# WR_LINK.net
KiCad netlist of a schematic drawn in Altium Designer
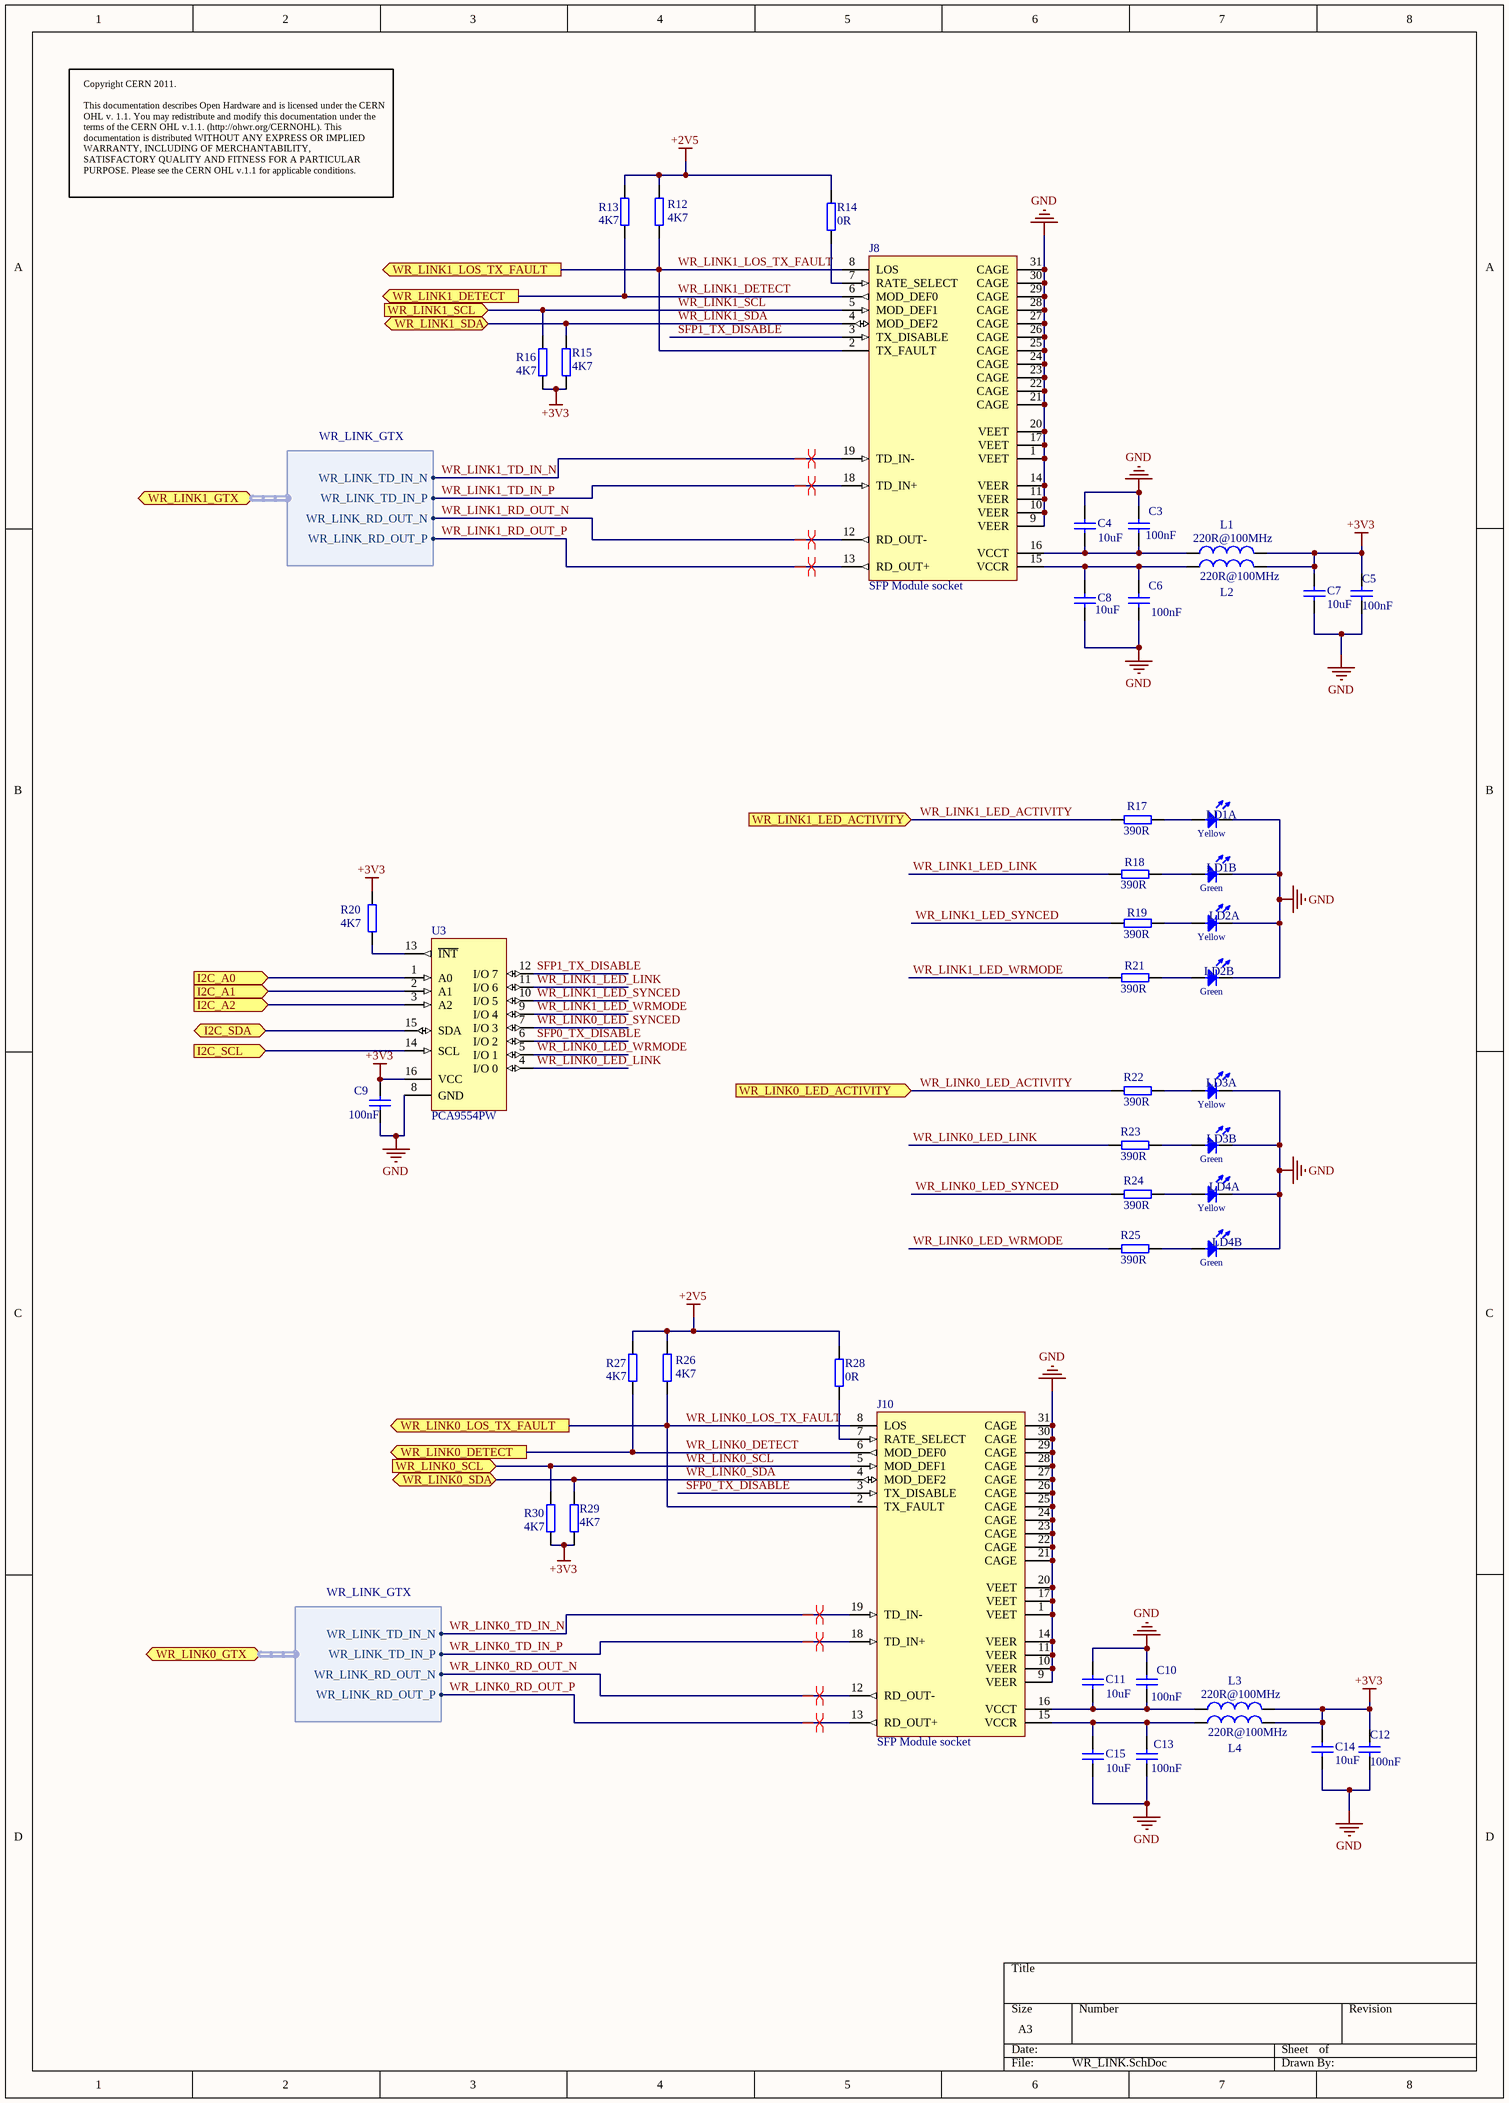
[diagram p0: WR_LINK.SchDoc]

(export (version "E")
  (design (tool "Eeschema 10.0.6"))
  (components
    (comp (ref "C3")
      (value "100nF")
      (footprint "CC1608-0603")
      (description "Capacitor")
      (fields
        (field (name "TOLERANCE") "±10%")
        (field (name "VOLTAGE") "16V")
        (field (name "PUBLISHER") "Altium Limited")
      )
      (libsource (lib "wr_switch") (part "Cap"))
    )
    (comp (ref "C4")
      (value "10uF")
      (footprint "CC2012-0805")
      (description "Capacitor")
      (fields
        (field (name "TOLERANCE") "±10%")
        (field (name "VOLTAGE") "16V")
        (field (name "PUBLISHER") "Altium Limited")
      )
      (libsource (lib "wr_switch") (part "Cap"))
    )
    (comp (ref "C5")
      (value "100nF")
      (footprint "CC1608-0603")
      (description "Capacitor")
      (fields
        (field (name "TOLERANCE") "±10%")
        (field (name "VOLTAGE") "16V")
        (field (name "PUBLISHER") "Altium Limited")
      )
      (libsource (lib "wr_switch") (part "Cap"))
    )
    (comp (ref "C6")
      (value "100nF")
      (footprint "CC1608-0603")
      (description "Capacitor")
      (fields
        (field (name "TOLERANCE") "±10%")
        (field (name "VOLTAGE") "16V")
        (field (name "PUBLISHER") "Altium Limited")
      )
      (libsource (lib "wr_switch") (part "Cap"))
    )
    (comp (ref "C7")
      (value "10uF")
      (footprint "CC1608-0603")
      (description "Capacitor")
      (fields
        (field (name "TOLERANCE") "±20%")
        (field (name "VOLTAGE") "6.3V")
        (field (name "PUBLISHER") "Altium Limited")
      )
      (libsource (lib "wr_switch") (part "Cap"))
    )
    (comp (ref "C8")
      (value "10uF")
      (footprint "CC2012-0805")
      (description "Capacitor")
      (fields
        (field (name "TOLERANCE") "±10%")
        (field (name "VOLTAGE") "16V")
        (field (name "PUBLISHER") "Altium Limited")
      )
      (libsource (lib "wr_switch") (part "Cap"))
    )
    (comp (ref "C9")
      (value "100nF")
      (footprint "CC1608-0603")
      (description "Capacitor")
      (fields
        (field (name "TOLERANCE") "±10%")
        (field (name "VOLTAGE") "16V")
        (field (name "PUBLISHER") "Altium Limited")
      )
      (libsource (lib "wr_switch") (part "Cap"))
    )
    (comp (ref "C10")
      (value "100nF")
      (footprint "CC1608-0603")
      (description "Capacitor")
      (fields
        (field (name "TOLERANCE") "±10%")
        (field (name "VOLTAGE") "16V")
        (field (name "PUBLISHER") "Altium Limited")
      )
      (libsource (lib "wr_switch") (part "Cap"))
    )
    (comp (ref "C11")
      (value "10uF")
      (footprint "CC2012-0805")
      (description "Capacitor")
      (fields
        (field (name "TOLERANCE") "±10%")
        (field (name "VOLTAGE") "16V")
        (field (name "PUBLISHER") "Altium Limited")
      )
      (libsource (lib "wr_switch") (part "Cap"))
    )
    (comp (ref "C12")
      (value "100nF")
      (footprint "CC1608-0603")
      (description "Capacitor")
      (fields
        (field (name "TOLERANCE") "±10%")
        (field (name "VOLTAGE") "16V")
        (field (name "PUBLISHER") "Altium Limited")
      )
      (libsource (lib "wr_switch") (part "Cap"))
    )
    (comp (ref "C13")
      (value "100nF")
      (footprint "CC1608-0603")
      (description "Capacitor")
      (fields
        (field (name "TOLERANCE") "±10%")
        (field (name "VOLTAGE") "16V")
        (field (name "PUBLISHER") "Altium Limited")
      )
      (libsource (lib "wr_switch") (part "Cap"))
    )
    (comp (ref "C14")
      (value "10uF")
      (footprint "CC1608-0603")
      (description "Capacitor")
      (fields
        (field (name "TOLERANCE") "±20%")
        (field (name "VOLTAGE") "6.3V")
        (field (name "PUBLISHER") "Altium Limited")
      )
      (libsource (lib "wr_switch") (part "Cap"))
    )
    (comp (ref "C15")
      (value "10uF")
      (footprint "CC2012-0805")
      (description "Capacitor")
      (fields
        (field (name "TOLERANCE") "±10%")
        (field (name "VOLTAGE") "16V")
        (field (name "PUBLISHER") "Altium Limited")
      )
      (libsource (lib "wr_switch") (part "Cap"))
    )
    (comp (ref "J8")
      (value "SFP Module socket")
      (footprint "7S_WR:SFP_SINGLE_PORT")
      (description "Socket for SFP module")
      (libsource (lib "wr_switch") (part "SFP_SOCKET_SINGLE"))
    )
    (comp (ref "J10")
      (value "SFP Module socket")
      (footprint "7S_WR:SFP_SINGLE_PORT")
      (description "Socket for SFP module")
      (libsource (lib "wr_switch") (part "SFP_SOCKET_SINGLE"))
    )
    (comp (ref "L1")
      (value "220R@100MHz Ferrite Bead")
      (footprint "0603")
      (description "ferrite bead")
      (fields (field (name "IMPEDANCE") "220R@100MHz"))
      (libsource (lib "wr_switch") (part "L_FERRITE_BEAD"))
    )
    (comp (ref "L2")
      (value "220R@100MHz Ferrite Bead")
      (footprint "0603")
      (description "ferrite bead")
      (fields (field (name "IMPEDANCE") "220R@100MHz"))
      (libsource (lib "wr_switch") (part "L_FERRITE_BEAD"))
    )
    (comp (ref "L3")
      (value "220R@100MHz Ferrite Bead")
      (footprint "0603")
      (description "ferrite bead")
      (fields (field (name "IMPEDANCE") "220R@100MHz"))
      (libsource (lib "wr_switch") (part "L_FERRITE_BEAD"))
    )
    (comp (ref "L4")
      (value "220R@100MHz Ferrite Bead")
      (footprint "0603")
      (description "ferrite bead")
      (fields (field (name "IMPEDANCE") "220R@100MHz"))
      (libsource (lib "wr_switch") (part "L_FERRITE_BEAD"))
    )
    (comp (ref "LD1")
      (value "Green/Yellow")
      (footprint "7S_WR:LED_DIALIGHT_591-3x0x-0xx")
      (description "Bi-Color LED SMD")
      (libsource (lib "wr_switch") (part "LED_DIALIGHT_591-3x0x"))
    )
    (comp (ref "LD2")
      (value "Green/Yellow")
      (footprint "7S_WR:LED_DIALIGHT_591-3x0x-0xx")
      (description "Bi-Color LED SMD")
      (libsource (lib "wr_switch") (part "LED_DIALIGHT_591-3x0x"))
    )
    (comp (ref "LD3")
      (value "Green/Yellow")
      (footprint "7S_WR:LED_DIALIGHT_591-3x0x-0xx")
      (description "Bi-Color LED SMD")
      (libsource (lib "wr_switch") (part "LED_DIALIGHT_591-3x0x"))
    )
    (comp (ref "LD4")
      (value "Green/Yellow")
      (footprint "7S_WR:LED_DIALIGHT_591-3x0x-0xx")
      (description "Bi-Color LED SMD")
      (libsource (lib "wr_switch") (part "LED_DIALIGHT_591-3x0x"))
    )
    (comp (ref "R12")
      (value "4K7")
      (footprint "0603")
      (description "SMD Resistor")
      (fields (field (name "TOLERANCE") "±1%"))
      (libsource (lib "wr_switch") (part "RES_SMD"))
    )
    (comp (ref "R13")
      (value "4K7")
      (footprint "0603")
      (description "SMD Resistor")
      (fields (field (name "TOLERANCE") "±1%"))
      (libsource (lib "wr_switch") (part "RES_SMD"))
    )
    (comp (ref "R14")
      (value "0R")
      (footprint "0603")
      (description "SMD Resistor")
      (libsource (lib "wr_switch") (part "RES_SMD"))
    )
    (comp (ref "R15")
      (value "4K7")
      (footprint "0603")
      (description "SMD Resistor")
      (fields (field (name "TOLERANCE") "±1%"))
      (libsource (lib "wr_switch") (part "RES_SMD"))
    )
    (comp (ref "R16")
      (value "4K7")
      (footprint "0603")
      (description "SMD Resistor")
      (fields (field (name "TOLERANCE") "±1%"))
      (libsource (lib "wr_switch") (part "RES_SMD"))
    )
    (comp (ref "R17")
      (value "390R")
      (footprint "0603")
      (description "SMD Resistor")
      (fields (field (name "TOLERANCE") "±1%"))
      (libsource (lib "wr_switch") (part "RES_SMD"))
    )
    (comp (ref "R18")
      (value "390R")
      (footprint "0603")
      (description "SMD Resistor")
      (fields (field (name "TOLERANCE") "±1%"))
      (libsource (lib "wr_switch") (part "RES_SMD"))
    )
    (comp (ref "R19")
      (value "390R")
      (footprint "0603")
      (description "SMD Resistor")
      (fields (field (name "TOLERANCE") "±1%"))
      (libsource (lib "wr_switch") (part "RES_SMD"))
    )
    (comp (ref "R20")
      (value "4K7")
      (footprint "0603")
      (description "SMD Resistor")
      (fields (field (name "TOLERANCE") "±1%"))
      (libsource (lib "wr_switch") (part "RES_SMD"))
    )
    (comp (ref "R21")
      (value "390R")
      (footprint "0603")
      (description "SMD Resistor")
      (fields (field (name "TOLERANCE") "±1%"))
      (libsource (lib "wr_switch") (part "RES_SMD"))
    )
    (comp (ref "R22")
      (value "390R")
      (footprint "0603")
      (description "SMD Resistor")
      (fields (field (name "TOLERANCE") "±1%"))
      (libsource (lib "wr_switch") (part "RES_SMD"))
    )
    (comp (ref "R23")
      (value "390R")
      (footprint "0603")
      (description "SMD Resistor")
      (fields (field (name "TOLERANCE") "±1%"))
      (libsource (lib "wr_switch") (part "RES_SMD"))
    )
    (comp (ref "R24")
      (value "390R")
      (footprint "0603")
      (description "SMD Resistor")
      (fields (field (name "TOLERANCE") "±1%"))
      (libsource (lib "wr_switch") (part "RES_SMD"))
    )
    (comp (ref "R25")
      (value "390R")
      (footprint "0603")
      (description "SMD Resistor")
      (fields (field (name "TOLERANCE") "±1%"))
      (libsource (lib "wr_switch") (part "RES_SMD"))
    )
    (comp (ref "R26")
      (value "4K7")
      (footprint "0603")
      (description "SMD Resistor")
      (fields (field (name "TOLERANCE") "±1%"))
      (libsource (lib "wr_switch") (part "RES_SMD"))
    )
    (comp (ref "R27")
      (value "4K7")
      (footprint "0603")
      (description "SMD Resistor")
      (fields (field (name "TOLERANCE") "±1%"))
      (libsource (lib "wr_switch") (part "RES_SMD"))
    )
    (comp (ref "R28")
      (value "0R")
      (footprint "0603")
      (description "SMD Resistor")
      (libsource (lib "wr_switch") (part "RES_SMD"))
    )
    (comp (ref "R29")
      (value "4K7")
      (footprint "0603")
      (description "SMD Resistor")
      (fields (field (name "TOLERANCE") "±1%"))
      (libsource (lib "wr_switch") (part "RES_SMD"))
    )
    (comp (ref "R30")
      (value "4K7")
      (footprint "0603")
      (description "SMD Resistor")
      (fields (field (name "TOLERANCE") "±1%"))
      (libsource (lib "wr_switch") (part "RES_SMD"))
    )
    (comp (ref "U3")
      (value "PCA9554PW")
      (footprint "SOP65P640X120-16N")
      (description "8-bit I2C-bus SMBus I/O port with interrupt")
      (libsource (lib "wr_switch") (part "PCA9554D"))
    )
  )
  (nets
    (net (code "2") (name "+2V5") (class "Default")
      (node (ref "R12") (pin "2") (pinfunction "2_2") (pintype "passive"))
      (node (ref "R13") (pin "2") (pinfunction "2_2") (pintype "passive"))
      (node (ref "R14") (pin "1") (pinfunction "1_1") (pintype "passive"))
      (node (ref "R26") (pin "2") (pinfunction "2_2") (pintype "passive"))
      (node (ref "R27") (pin "2") (pinfunction "2_2") (pintype "passive"))
      (node (ref "R28") (pin "1") (pinfunction "1_1") (pintype "passive"))
    )
    (net (code "3") (name "+3V3") (class "Default")
      (node (ref "C12") (pin "1") (pinfunction "1_1") (pintype "passive"))
      (node (ref "C14") (pin "1") (pinfunction "1_1") (pintype "passive"))
      (node (ref "C5") (pin "1") (pinfunction "1_1") (pintype "passive"))
      (node (ref "C7") (pin "1") (pinfunction "1_1") (pintype "passive"))
      (node (ref "C9") (pin "1") (pinfunction "1_1") (pintype "passive"))
      (node (ref "L1") (pin "2") (pinfunction "2_2") (pintype "passive"))
      (node (ref "L2") (pin "2") (pinfunction "2_2") (pintype "passive"))
      (node (ref "L3") (pin "2") (pinfunction "2_2") (pintype "passive"))
      (node (ref "L4") (pin "2") (pinfunction "2_2") (pintype "passive"))
      (node (ref "R15") (pin "2") (pinfunction "2_2") (pintype "passive"))
      (node (ref "R16") (pin "2") (pinfunction "2_2") (pintype "passive"))
      (node (ref "R20") (pin "2") (pinfunction "2_2") (pintype "passive"))
      (node (ref "R29") (pin "2") (pinfunction "2_2") (pintype "passive"))
      (node (ref "R30") (pin "2") (pinfunction "2_2") (pintype "passive"))
      (node (ref "U3") (pin "16") (pinfunction "VCC_16") (pintype "power_in"))
    )
    (net (code "4") (name "/I2C_A0") (class "Default")
      (node (ref "U3") (pin "1") (pinfunction "A0_1") (pintype "input"))
    )
    (net (code "5") (name "/I2C_A1") (class "Default")
      (node (ref "U3") (pin "2") (pinfunction "A1_2") (pintype "input"))
    )
    (net (code "6") (name "/I2C_A2") (class "Default")
      (node (ref "U3") (pin "3") (pinfunction "A2_3") (pintype "input"))
    )
    (net (code "7") (name "/I2C_SCL") (class "Default")
      (node (ref "U3") (pin "14") (pinfunction "SCL_14") (pintype "input"))
    )
    (net (code "8") (name "/I2C_SDA") (class "Default")
      (node (ref "U3") (pin "15") (pinfunction "SDA_15") (pintype "bidirectional"))
    )
    (net (code "9") (name "/SFP0_TX_DISABLE") (class "Default")
      (node (ref "J10") (pin "3") (pinfunction "TX_DISABLE_3") (pintype "input"))
      (node (ref "U3") (pin "6") (pinfunction "I/O_2_6") (pintype "bidirectional"))
    )
    (net (code "10") (name "/SFP1_TX_DISABLE") (class "Default")
      (node (ref "J8") (pin "3") (pinfunction "TX_DISABLE_3") (pintype "input"))
      (node (ref "U3") (pin "12") (pinfunction "I/O_7_12") (pintype "bidirectional"))
    )
    (net (code "11") (name "/WR_LINK0_DETECT") (class "Default")
      (node (ref "J10") (pin "6") (pinfunction "MOD_DEF0_6") (pintype "output"))
      (node (ref "R27") (pin "1") (pinfunction "1_1") (pintype "passive"))
    )
    (net (code "12") (name "/WR_LINK0_LED_ACTIVITY") (class "Default")
      (node (ref "R22") (pin "2") (pinfunction "2_2") (pintype "passive"))
    )
    (net (code "13") (name "/WR_LINK0_LED_LINK") (class "Default")
      (node (ref "R23") (pin "2") (pinfunction "2_2") (pintype "passive"))
      (node (ref "U3") (pin "4") (pinfunction "I/O_0_4") (pintype "bidirectional"))
    )
    (net (code "14") (name "/WR_LINK0_LED_SYNCED") (class "Default")
      (node (ref "R24") (pin "2") (pinfunction "2_2") (pintype "passive"))
      (node (ref "U3") (pin "7") (pinfunction "I/O_3_7") (pintype "bidirectional"))
    )
    (net (code "15") (name "/WR_LINK0_LED_WRMODE") (class "Default")
      (node (ref "R25") (pin "2") (pinfunction "2_2") (pintype "passive"))
      (node (ref "U3") (pin "5") (pinfunction "I/O_1_5") (pintype "bidirectional"))
    )
    (net (code "16") (name "/WR_LINK0_LOS_TX_FAULT") (class "Default")
      (node (ref "J10") (pin "2") (pinfunction "TX_FAULT_2") (pintype "open_collector"))
      (node (ref "J10") (pin "8") (pinfunction "LOS_8") (pintype "open_collector"))
      (node (ref "R26") (pin "1") (pinfunction "1_1") (pintype "passive"))
    )
    (net (code "17") (name "/WR_LINK0_RD_OUT_N") (class "Default")
      (node (ref "J10") (pin "12") (pinfunction "RD_OUT-_12") (pintype "output"))
    )
    (net (code "18") (name "/WR_LINK0_RD_OUT_P") (class "Default")
      (node (ref "J10") (pin "13") (pinfunction "RD_OUT+_13") (pintype "output"))
    )
    (net (code "19") (name "/WR_LINK0_SCL") (class "Default")
      (node (ref "J10") (pin "5") (pinfunction "MOD_DEF1_5") (pintype "input"))
      (node (ref "R30") (pin "1") (pinfunction "1_1") (pintype "passive"))
    )
    (net (code "20") (name "/WR_LINK0_SDA") (class "Default")
      (node (ref "J10") (pin "4") (pinfunction "MOD_DEF2_4") (pintype "bidirectional"))
      (node (ref "R29") (pin "1") (pinfunction "1_1") (pintype "passive"))
    )
    (net (code "21") (name "/WR_LINK0_TD_IN_N") (class "Default")
      (node (ref "J10") (pin "19") (pinfunction "TD_IN-_19") (pintype "input"))
    )
    (net (code "22") (name "/WR_LINK0_TD_IN_P") (class "Default")
      (node (ref "J10") (pin "18") (pinfunction "TD_IN+_18") (pintype "input"))
    )
    (net (code "23") (name "/WR_LINK1_DETECT") (class "Default")
      (node (ref "J8") (pin "6") (pinfunction "MOD_DEF0_6") (pintype "output"))
      (node (ref "R13") (pin "1") (pinfunction "1_1") (pintype "passive"))
    )
    (net (code "24") (name "/WR_LINK1_LED_ACTIVITY") (class "Default")
      (node (ref "R17") (pin "2") (pinfunction "2_2") (pintype "passive"))
    )
    (net (code "25") (name "/WR_LINK1_LED_LINK") (class "Default")
      (node (ref "R18") (pin "2") (pinfunction "2_2") (pintype "passive"))
      (node (ref "U3") (pin "11") (pinfunction "I/O_6_11") (pintype "bidirectional"))
    )
    (net (code "26") (name "/WR_LINK1_LED_SYNCED") (class "Default")
      (node (ref "R19") (pin "2") (pinfunction "2_2") (pintype "passive"))
      (node (ref "U3") (pin "10") (pinfunction "I/O_5_10") (pintype "bidirectional"))
    )
    (net (code "27") (name "/WR_LINK1_LED_WRMODE") (class "Default")
      (node (ref "R21") (pin "2") (pinfunction "2_2") (pintype "passive"))
      (node (ref "U3") (pin "9") (pinfunction "I/O_4_9") (pintype "bidirectional"))
    )
    (net (code "28") (name "/WR_LINK1_LOS_TX_FAULT") (class "Default")
      (node (ref "J8") (pin "2") (pinfunction "TX_FAULT_2") (pintype "open_collector"))
      (node (ref "J8") (pin "8") (pinfunction "LOS_8") (pintype "open_collector"))
      (node (ref "R12") (pin "1") (pinfunction "1_1") (pintype "passive"))
    )
    (net (code "29") (name "/WR_LINK1_RD_OUT_N") (class "Default")
      (node (ref "J8") (pin "12") (pinfunction "RD_OUT-_12") (pintype "output"))
    )
    (net (code "30") (name "/WR_LINK1_RD_OUT_P") (class "Default")
      (node (ref "J8") (pin "13") (pinfunction "RD_OUT+_13") (pintype "output"))
    )
    (net (code "31") (name "/WR_LINK1_SCL") (class "Default")
      (node (ref "J8") (pin "5") (pinfunction "MOD_DEF1_5") (pintype "input"))
      (node (ref "R16") (pin "1") (pinfunction "1_1") (pintype "passive"))
    )
    (net (code "32") (name "/WR_LINK1_SDA") (class "Default")
      (node (ref "J8") (pin "4") (pinfunction "MOD_DEF2_4") (pintype "bidirectional"))
      (node (ref "R15") (pin "1") (pinfunction "1_1") (pintype "passive"))
    )
    (net (code "33") (name "/WR_LINK1_TD_IN_N") (class "Default")
      (node (ref "J8") (pin "19") (pinfunction "TD_IN-_19") (pintype "input"))
    )
    (net (code "34") (name "/WR_LINK1_TD_IN_P") (class "Default")
      (node (ref "J8") (pin "18") (pinfunction "TD_IN+_18") (pintype "input"))
    )
    (net (code "36") (name "GND") (class "Default")
      (node (ref "C10") (pin "1") (pinfunction "1_1") (pintype "passive"))
      (node (ref "C11") (pin "2") (pinfunction "2_2") (pintype "passive"))
      (node (ref "C12") (pin "2") (pinfunction "2_2") (pintype "passive"))
      (node (ref "C13") (pin "2") (pinfunction "2_2") (pintype "passive"))
      (node (ref "C14") (pin "2") (pinfunction "2_2") (pintype "passive"))
      (node (ref "C15") (pin "1") (pinfunction "1_1") (pintype "passive"))
      (node (ref "C3") (pin "1") (pinfunction "1_1") (pintype "passive"))
      (node (ref "C4") (pin "2") (pinfunction "2_2") (pintype "passive"))
      (node (ref "C5") (pin "2") (pinfunction "2_2") (pintype "passive"))
      (node (ref "C6") (pin "2") (pinfunction "2_2") (pintype "passive"))
      (node (ref "C7") (pin "2") (pinfunction "2_2") (pintype "passive"))
      (node (ref "C8") (pin "1") (pinfunction "1_1") (pintype "passive"))
      (node (ref "C9") (pin "2") (pinfunction "2_2") (pintype "passive"))
      (node (ref "J10") (pin "1") (pinfunction "VEET_1") (pintype "power_in"))
      (node (ref "J10") (pin "10") (pinfunction "VEER_10") (pintype "power_in"))
      (node (ref "J10") (pin "11") (pinfunction "VEER_11") (pintype "power_in"))
      (node (ref "J10") (pin "14") (pinfunction "VEER_14") (pintype "power_in"))
      (node (ref "J10") (pin "17") (pinfunction "VEET_17") (pintype "power_in"))
      (node (ref "J10") (pin "20") (pinfunction "VEET_20") (pintype "power_in"))
      (node (ref "J10") (pin "21") (pinfunction "CAGE_21") (pintype "power_in"))
      (node (ref "J10") (pin "22") (pinfunction "CAGE_22") (pintype "power_in"))
      (node (ref "J10") (pin "23") (pinfunction "CAGE_23") (pintype "power_in"))
      (node (ref "J10") (pin "24") (pinfunction "CAGE_24") (pintype "power_in"))
      (node (ref "J10") (pin "25") (pinfunction "CAGE_25") (pintype "power_in"))
      (node (ref "J10") (pin "26") (pinfunction "CAGE_26") (pintype "power_in"))
      (node (ref "J10") (pin "27") (pinfunction "CAGE_27") (pintype "power_in"))
      (node (ref "J10") (pin "28") (pinfunction "CAGE_28") (pintype "power_in"))
      (node (ref "J10") (pin "29") (pinfunction "CAGE_29") (pintype "power_in"))
      (node (ref "J10") (pin "30") (pinfunction "CAGE_30") (pintype "power_in"))
      (node (ref "J10") (pin "31") (pinfunction "CAGE_31") (pintype "power_in"))
      (node (ref "J10") (pin "9") (pinfunction "VEER_9") (pintype "power_in"))
      (node (ref "J8") (pin "1") (pinfunction "VEET_1") (pintype "power_in"))
      (node (ref "J8") (pin "10") (pinfunction "VEER_10") (pintype "power_in"))
      (node (ref "J8") (pin "11") (pinfunction "VEER_11") (pintype "power_in"))
      (node (ref "J8") (pin "14") (pinfunction "VEER_14") (pintype "power_in"))
      (node (ref "J8") (pin "17") (pinfunction "VEET_17") (pintype "power_in"))
      (node (ref "J8") (pin "20") (pinfunction "VEET_20") (pintype "power_in"))
      (node (ref "J8") (pin "21") (pinfunction "CAGE_21") (pintype "power_in"))
      (node (ref "J8") (pin "22") (pinfunction "CAGE_22") (pintype "power_in"))
      (node (ref "J8") (pin "23") (pinfunction "CAGE_23") (pintype "power_in"))
      (node (ref "J8") (pin "24") (pinfunction "CAGE_24") (pintype "power_in"))
      (node (ref "J8") (pin "25") (pinfunction "CAGE_25") (pintype "power_in"))
      (node (ref "J8") (pin "26") (pinfunction "CAGE_26") (pintype "power_in"))
      (node (ref "J8") (pin "27") (pinfunction "CAGE_27") (pintype "power_in"))
      (node (ref "J8") (pin "28") (pinfunction "CAGE_28") (pintype "power_in"))
      (node (ref "J8") (pin "29") (pinfunction "CAGE_29") (pintype "power_in"))
      (node (ref "J8") (pin "30") (pinfunction "CAGE_30") (pintype "power_in"))
      (node (ref "J8") (pin "31") (pinfunction "CAGE_31") (pintype "power_in"))
      (node (ref "J8") (pin "9") (pinfunction "VEER_9") (pintype "power_in"))
      (node (ref "LD1") (pin "1") (pinfunction "C_1") (pintype "passive"))
      (node (ref "LD1") (pin "4") (pinfunction "C_4") (pintype "passive"))
      (node (ref "LD2") (pin "1") (pinfunction "C_1") (pintype "passive"))
      (node (ref "LD2") (pin "4") (pinfunction "C_4") (pintype "passive"))
      (node (ref "LD3") (pin "1") (pinfunction "C_1") (pintype "passive"))
      (node (ref "LD3") (pin "4") (pinfunction "C_4") (pintype "passive"))
      (node (ref "LD4") (pin "1") (pinfunction "C_1") (pintype "passive"))
      (node (ref "LD4") (pin "4") (pinfunction "C_4") (pintype "passive"))
      (node (ref "U3") (pin "8") (pinfunction "GND_8") (pintype "power_in"))
    )
    (net (code "37") (name "Net-(J8-RATE_SELECT)") (class "Default")
      (node (ref "J8") (pin "7") (pinfunction "RATE_SELECT_7") (pintype "input"))
      (node (ref "R14") (pin "2") (pinfunction "2_2") (pintype "passive"))
    )
    (net (code "38") (name "Net-(J8-VCCR)") (class "Default")
      (node (ref "C6") (pin "1") (pinfunction "1_1") (pintype "passive"))
      (node (ref "C8") (pin "2") (pinfunction "2_2") (pintype "passive"))
      (node (ref "J8") (pin "15") (pinfunction "VCCR_15") (pintype "power_in"))
      (node (ref "L2") (pin "1") (pinfunction "1_1") (pintype "passive"))
    )
    (net (code "39") (name "Net-(J8-VCCT)") (class "Default")
      (node (ref "C3") (pin "2") (pinfunction "2_2") (pintype "passive"))
      (node (ref "C4") (pin "1") (pinfunction "1_1") (pintype "passive"))
      (node (ref "J8") (pin "16") (pinfunction "VCCT_16") (pintype "power_in"))
      (node (ref "L1") (pin "1") (pinfunction "1_1") (pintype "passive"))
    )
    (net (code "40") (name "Net-(J10-RATE_SELECT)") (class "Default")
      (node (ref "J10") (pin "7") (pinfunction "RATE_SELECT_7") (pintype "input"))
      (node (ref "R28") (pin "2") (pinfunction "2_2") (pintype "passive"))
    )
    (net (code "41") (name "Net-(J10-VCCR)") (class "Default")
      (node (ref "C13") (pin "1") (pinfunction "1_1") (pintype "passive"))
      (node (ref "C15") (pin "2") (pinfunction "2_2") (pintype "passive"))
      (node (ref "J10") (pin "15") (pinfunction "VCCR_15") (pintype "power_in"))
      (node (ref "L4") (pin "1") (pinfunction "1_1") (pintype "passive"))
    )
    (net (code "42") (name "Net-(J10-VCCT)") (class "Default")
      (node (ref "C10") (pin "2") (pinfunction "2_2") (pintype "passive"))
      (node (ref "C11") (pin "1") (pinfunction "1_1") (pintype "passive"))
      (node (ref "J10") (pin "16") (pinfunction "VCCT_16") (pintype "power_in"))
      (node (ref "L3") (pin "1") (pinfunction "1_1") (pintype "passive"))
    )
    (net (code "43") (name "Net-(LD1A-A)") (class "Default")
      (node (ref "LD1") (pin "2") (pinfunction "A_2") (pintype "passive"))
      (node (ref "R17") (pin "1") (pinfunction "1_1") (pintype "passive"))
    )
    (net (code "44") (name "Net-(LD1B-A)") (class "Default")
      (node (ref "LD1") (pin "3") (pinfunction "A_3") (pintype "passive"))
      (node (ref "R18") (pin "1") (pinfunction "1_1") (pintype "passive"))
    )
    (net (code "45") (name "Net-(LD2A-A)") (class "Default")
      (node (ref "LD2") (pin "2") (pinfunction "A_2") (pintype "passive"))
      (node (ref "R19") (pin "1") (pinfunction "1_1") (pintype "passive"))
    )
    (net (code "46") (name "Net-(LD2B-A)") (class "Default")
      (node (ref "LD2") (pin "3") (pinfunction "A_3") (pintype "passive"))
      (node (ref "R21") (pin "1") (pinfunction "1_1") (pintype "passive"))
    )
    (net (code "47") (name "Net-(LD3A-A)") (class "Default")
      (node (ref "LD3") (pin "2") (pinfunction "A_2") (pintype "passive"))
      (node (ref "R22") (pin "1") (pinfunction "1_1") (pintype "passive"))
    )
    (net (code "48") (name "Net-(LD3B-A)") (class "Default")
      (node (ref "LD3") (pin "3") (pinfunction "A_3") (pintype "passive"))
      (node (ref "R23") (pin "1") (pinfunction "1_1") (pintype "passive"))
    )
    (net (code "49") (name "Net-(LD4A-A)") (class "Default")
      (node (ref "LD4") (pin "2") (pinfunction "A_2") (pintype "passive"))
      (node (ref "R24") (pin "1") (pinfunction "1_1") (pintype "passive"))
    )
    (net (code "50") (name "Net-(LD4B-A)") (class "Default")
      (node (ref "LD4") (pin "3") (pinfunction "A_3") (pintype "passive"))
      (node (ref "R25") (pin "1") (pinfunction "1_1") (pintype "passive"))
    )
    (net (code "51") (name "Net-(U3-~{INT})") (class "Default")
      (node (ref "R20") (pin "1") (pinfunction "1_1") (pintype "passive"))
      (node (ref "U3") (pin "13") (pinfunction "~{INT}_13") (pintype "output"))
    )
  )
)
